# RS485-Breakout-v13.net
KiCad netlist of a schematic drawn in EAGLE
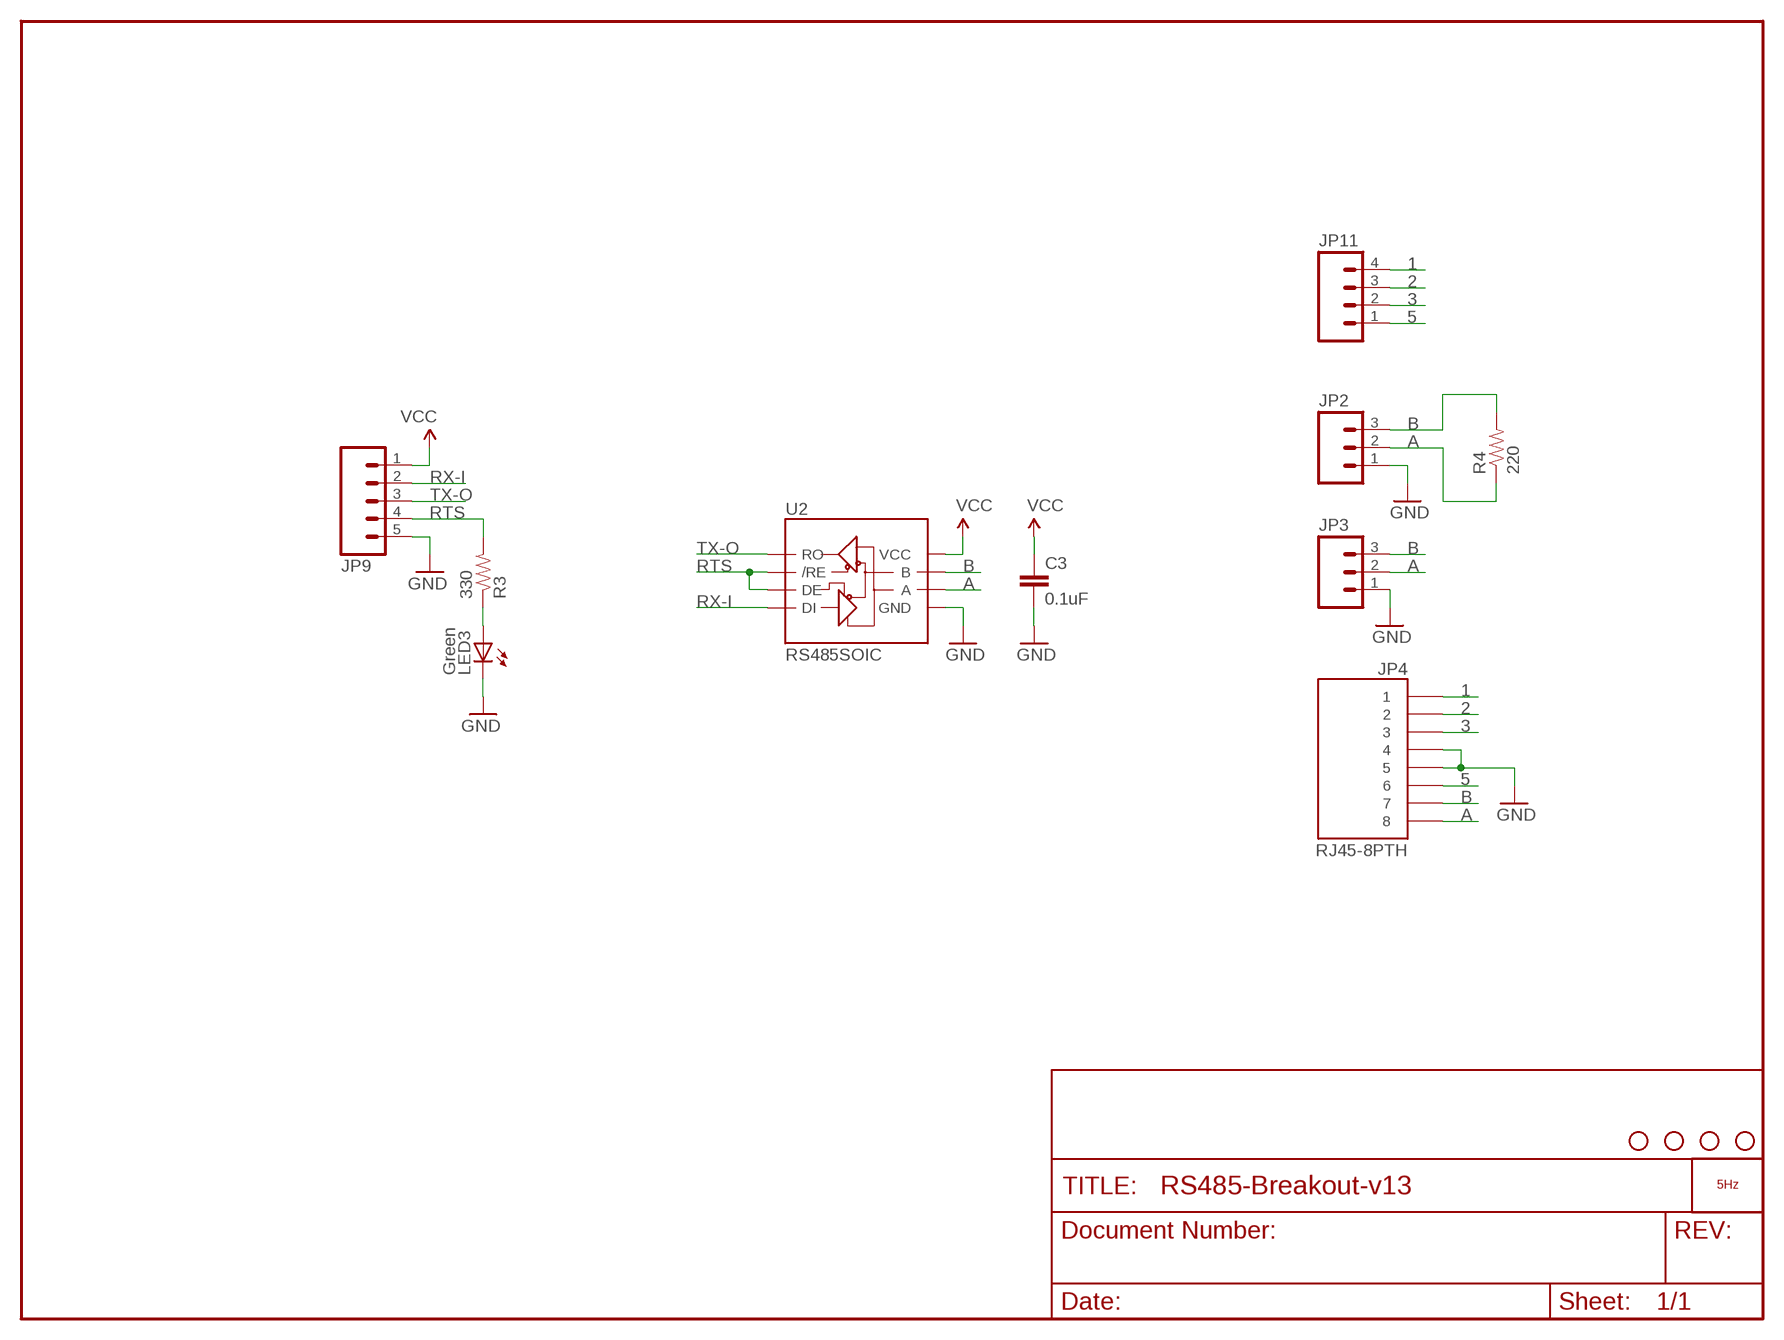
[diagram p0: schematic, sheet 1]

(export (version "E")
  (design (tool "Eeschema 10.0.6"))
  (components
    (comp (ref "C3")
      (value "0.1uF")
      (footprint "eagle-import:0402-CAP")
      (libsource (lib "eagle-import") (part "CAP0402-CAP"))
    )
    (comp (ref "JP1")
      (value "STAND-OFF")
      (footprint "eagle-import:STAND-OFF")
      (libsource (lib "eagle-import") (part "STAND-OFF"))
    )
    (comp (ref "JP2")
      (value "M03SCREW")
      (footprint "eagle-import:SCREWTERMINAL-3.5MM-3")
      (libsource (lib "eagle-import") (part "M03SCREW"))
    )
    (comp (ref "JP3")
      (value "M03PTH")
      (footprint "eagle-import:1X03")
      (libsource (lib "eagle-import") (part "M03PTH"))
    )
    (comp (ref "JP4")
      (value "RJ45-8PTH")
      (footprint "eagle-import:RJ45-8")
      (libsource (lib "eagle-import") (part "RJ45-8PTH"))
    )
    (comp (ref "JP6")
      (value "STAND-OFF")
      (footprint "eagle-import:STAND-OFF")
      (libsource (lib "eagle-import") (part "STAND-OFF"))
    )
    (comp (ref "JP7")
      (value "STAND-OFF")
      (footprint "eagle-import:STAND-OFF")
      (libsource (lib "eagle-import") (part "STAND-OFF"))
    )
    (comp (ref "JP8")
      (value "STAND-OFF")
      (footprint "eagle-import:STAND-OFF")
      (libsource (lib "eagle-import") (part "STAND-OFF"))
    )
    (comp (ref "JP9")
      (value "M05PTH")
      (footprint "eagle-import:1X05")
      (libsource (lib "eagle-import") (part "M05PTH"))
    )
    (comp (ref "JP11")
      (value "M04PTH")
      (footprint "eagle-import:1X04")
      (libsource (lib "eagle-import") (part "M04PTH"))
    )
    (comp (ref "LED3")
      (value "Green")
      (footprint "eagle-import:LED-0603")
      (libsource (lib "eagle-import") (part "LED0603"))
    )
    (comp (ref "LOGO1")
      (value "LOGO_5HZ_CIRC_3.5MM")
      (footprint "eagle-import:5HZ_LOGO_CIRC_3.5MM")
      (libsource (lib "eagle-import") (part "LOGO_5HZ_CIRC_3.5MM"))
    )
    (comp (ref "R3")
      (value "330")
      (footprint "eagle-import:0402-RES")
      (libsource (lib "eagle-import") (part "RESISTOR0402-RES"))
    )
    (comp (ref "R4")
      (value "220")
      (footprint "eagle-import:0402-RES")
      (libsource (lib "eagle-import") (part "RESISTOR0402-RES"))
    )
    (comp (ref "U2")
      (value "RS485SOIC")
      (footprint "eagle-import:SO08")
      (libsource (lib "eagle-import") (part "RS485SOIC"))
    )
  )
  (nets
    (net (code "1") (name "/1") (class "Default")
      (node (ref "JP11") (pin "4") (pinfunction "4_4") (pintype "passive"))
      (node (ref "JP4") (pin "1") (pinfunction "1_1") (pintype "bidirectional"))
    )
    (net (code "2") (name "/2") (class "Default")
      (node (ref "JP11") (pin "3") (pinfunction "3_3") (pintype "passive"))
      (node (ref "JP4") (pin "2") (pinfunction "2_2") (pintype "bidirectional"))
    )
    (net (code "3") (name "/3") (class "Default")
      (node (ref "JP11") (pin "2") (pinfunction "2_2") (pintype "passive"))
      (node (ref "JP4") (pin "3") (pinfunction "3_3") (pintype "bidirectional"))
    )
    (net (code "4") (name "/5") (class "Default")
      (node (ref "JP11") (pin "1") (pinfunction "1_1") (pintype "passive"))
      (node (ref "JP4") (pin "6") (pinfunction "6_6") (pintype "bidirectional"))
    )
    (net (code "5") (name "/A") (class "Default")
      (node (ref "JP2") (pin "2") (pinfunction "2_2") (pintype "passive"))
      (node (ref "JP3") (pin "2") (pinfunction "2_2") (pintype "passive"))
      (node (ref "JP4") (pin "8") (pinfunction "8_8") (pintype "bidirectional"))
      (node (ref "R4") (pin "1") (pinfunction "1_1") (pintype "passive"))
      (node (ref "U2") (pin "6") (pinfunction "A_6") (pintype "bidirectional"))
    )
    (net (code "6") (name "/B") (class "Default")
      (node (ref "JP2") (pin "3") (pinfunction "3_3") (pintype "passive"))
      (node (ref "JP3") (pin "3") (pinfunction "3_3") (pintype "passive"))
      (node (ref "JP4") (pin "7") (pinfunction "7_7") (pintype "bidirectional"))
      (node (ref "R4") (pin "2") (pinfunction "2_2") (pintype "passive"))
      (node (ref "U2") (pin "7") (pinfunction "B_7") (pintype "bidirectional"))
    )
    (net (code "7") (name "/RTS") (class "Default")
      (node (ref "JP9") (pin "4") (pinfunction "4_4") (pintype "passive"))
      (node (ref "R3") (pin "2") (pinfunction "2_2") (pintype "passive"))
      (node (ref "U2") (pin "2") (pinfunction "/RE_2") (pintype "bidirectional"))
      (node (ref "U2") (pin "3") (pinfunction "DE_3") (pintype "bidirectional"))
    )
    (net (code "8") (name "/RX-I") (class "Default")
      (node (ref "JP9") (pin "2") (pinfunction "2_2") (pintype "passive"))
      (node (ref "U2") (pin "4") (pinfunction "DI_4") (pintype "bidirectional"))
    )
    (net (code "9") (name "/TX-O") (class "Default")
      (node (ref "JP9") (pin "3") (pinfunction "3_3") (pintype "passive"))
      (node (ref "U2") (pin "1") (pinfunction "RO_1") (pintype "bidirectional"))
    )
    (net (code "10") (name "GND") (class "Default")
      (node (ref "C3") (pin "2") (pinfunction "2_2") (pintype "passive"))
      (node (ref "JP2") (pin "1") (pinfunction "1_1") (pintype "passive"))
      (node (ref "JP3") (pin "1") (pinfunction "1_1") (pintype "passive"))
      (node (ref "JP4") (pin "4") (pinfunction "4_4") (pintype "bidirectional"))
      (node (ref "JP4") (pin "5") (pinfunction "5_5") (pintype "bidirectional"))
      (node (ref "JP9") (pin "5") (pinfunction "5_5") (pintype "passive"))
      (node (ref "LED3") (pin "C") (pinfunction "C_C") (pintype "passive"))
      (node (ref "U2") (pin "5") (pinfunction "GND_5") (pintype "bidirectional"))
    )
    (net (code "11") (name "Net-(LED3-PadA)") (class "Default")
      (node (ref "LED3") (pin "A") (pinfunction "A_A") (pintype "passive"))
      (node (ref "R3") (pin "1") (pinfunction "1_1") (pintype "passive"))
    )
    (net (code "12") (name "VCC") (class "Default")
      (node (ref "C3") (pin "1") (pinfunction "1_1") (pintype "passive"))
      (node (ref "JP9") (pin "1") (pinfunction "1_1") (pintype "passive"))
      (node (ref "U2") (pin "8") (pinfunction "VCC_8") (pintype "bidirectional"))
    )
  )
)
